# stm32_debug_adapter.net
KiCad netlist of a schematic drawn in EAGLE
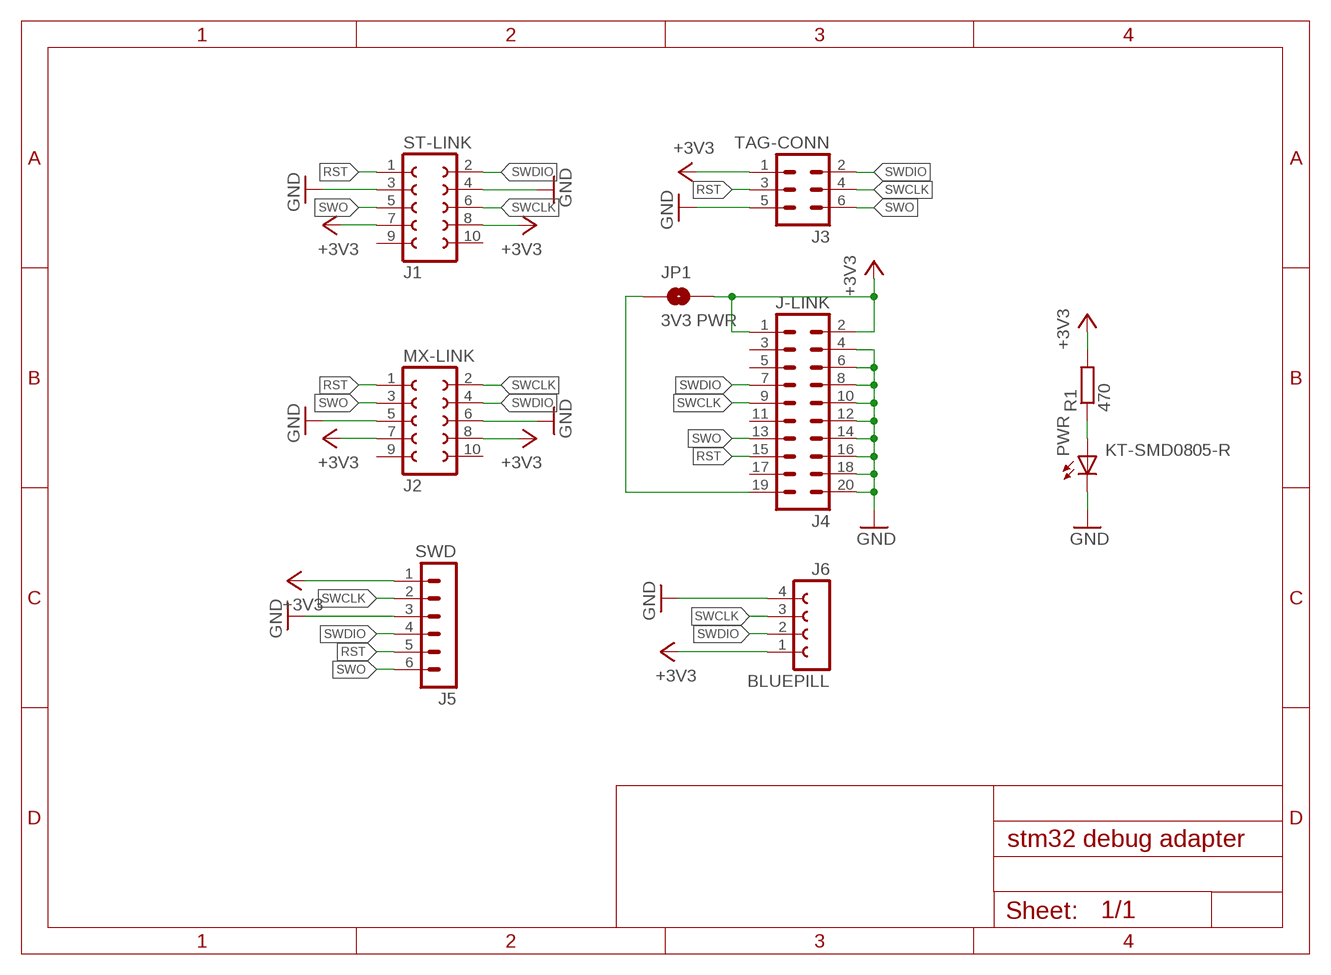
[diagram p0: schematic, sheet 1]

(export (version "E")
  (design (tool "Eeschema 10.0.6"))
  (components
    (comp (ref "J1")
      (value "ST-LINK")
      (footprint "eagle-import:FE05-2W")
      (libsource (lib "eagle-import") (part "FE05-2W"))
    )
    (comp (ref "J2")
      (value "MX-LINK")
      (footprint "eagle-import:FE05-2W")
      (libsource (lib "eagle-import") (part "FE05-2W"))
    )
    (comp (ref "J3")
      (value "TAG-CONN")
      (footprint "eagle-import:ML6")
      (libsource (lib "eagle-import") (part "ML6"))
    )
    (comp (ref "J4")
      (value "J-LINK")
      (footprint "eagle-import:ML20")
      (libsource (lib "eagle-import") (part "ML20"))
    )
    (comp (ref "J5")
      (value "SWD")
      (footprint "eagle-import:MA06-1")
      (libsource (lib "eagle-import") (part "MA06-1"))
    )
    (comp (ref "J6")
      (value "BLUEPILL")
      (footprint "eagle-import:FE04W")
      (libsource (lib "eagle-import") (part "FE04W"))
    )
    (comp (ref "JP1")
      (value "3V3 PWR")
      (footprint "eagle-import:SMT-JUMPER_2_NO_NO-SILK")
      (libsource (lib "eagle-import") (part "JUMPER-SMT_2_NO_NO-SILK"))
    )
    (comp (ref "PWR")
      (value "KT-SMD0805-R")
      (footprint "eagle-import:SML0805")
      (libsource (lib "eagle-import") (part "LEDSML0805"))
    )
    (comp (ref "R1")
      (value "470")
      (footprint "eagle-import:R0805")
      (libsource (lib "eagle-import") (part "R-EU_R0805"))
    )
  )
  (nets
    (net (code "1") (name "+3V3") (class "Default")
      (node (ref "J1") (pin "7") (pinfunction "7_7") (pintype "passive"))
      (node (ref "J1") (pin "8") (pinfunction "8_8") (pintype "passive"))
      (node (ref "J2") (pin "7") (pinfunction "7_7") (pintype "passive"))
      (node (ref "J2") (pin "8") (pinfunction "8_8") (pintype "passive"))
      (node (ref "J3") (pin "1") (pinfunction "1_1") (pintype "passive"))
      (node (ref "J4") (pin "1") (pinfunction "1_1") (pintype "passive"))
      (node (ref "J4") (pin "2") (pinfunction "2_2") (pintype "passive"))
      (node (ref "J5") (pin "1") (pinfunction "1_1") (pintype "passive"))
      (node (ref "J6") (pin "1") (pinfunction "1_1") (pintype "passive"))
      (node (ref "JP1") (pin "2") (pinfunction "2_2") (pintype "passive"))
      (node (ref "R1") (pin "2") (pinfunction "2_2") (pintype "passive"))
    )
    (net (code "2") (name "GND") (class "Default")
      (node (ref "J1") (pin "3") (pinfunction "3_3") (pintype "passive"))
      (node (ref "J1") (pin "4") (pinfunction "4_4") (pintype "passive"))
      (node (ref "J2") (pin "5") (pinfunction "5_5") (pintype "passive"))
      (node (ref "J2") (pin "6") (pinfunction "6_6") (pintype "passive"))
      (node (ref "J3") (pin "5") (pinfunction "5_5") (pintype "passive"))
      (node (ref "J4") (pin "10") (pinfunction "10_10") (pintype "passive"))
      (node (ref "J4") (pin "12") (pinfunction "12_12") (pintype "passive"))
      (node (ref "J4") (pin "14") (pinfunction "14_14") (pintype "passive"))
      (node (ref "J4") (pin "16") (pinfunction "16_16") (pintype "passive"))
      (node (ref "J4") (pin "18") (pinfunction "18_18") (pintype "passive"))
      (node (ref "J4") (pin "20") (pinfunction "20_20") (pintype "passive"))
      (node (ref "J4") (pin "4") (pinfunction "4_4") (pintype "passive"))
      (node (ref "J4") (pin "6") (pinfunction "6_6") (pintype "passive"))
      (node (ref "J4") (pin "8") (pinfunction "8_8") (pintype "passive"))
      (node (ref "J5") (pin "3") (pinfunction "3_3") (pintype "passive"))
      (node (ref "J6") (pin "4") (pinfunction "4_4") (pintype "passive"))
      (node (ref "PWR") (pin "C") (pinfunction "C_C") (pintype "passive"))
    )
    (net (code "3") (name "Net-(J4-Pad19)") (class "Default")
      (node (ref "J4") (pin "19") (pinfunction "19_19") (pintype "passive"))
      (node (ref "JP1") (pin "1") (pinfunction "1_1") (pintype "passive"))
    )
    (net (code "4") (name "Net-(PWR-PadA)") (class "Default")
      (node (ref "PWR") (pin "A") (pinfunction "A_A") (pintype "passive"))
      (node (ref "R1") (pin "1") (pinfunction "1_1") (pintype "passive"))
    )
    (net (code "5") (name "RST") (class "Default")
      (node (ref "J1") (pin "1") (pinfunction "1_1") (pintype "passive"))
      (node (ref "J2") (pin "1") (pinfunction "1_1") (pintype "passive"))
      (node (ref "J3") (pin "3") (pinfunction "3_3") (pintype "passive"))
      (node (ref "J4") (pin "15") (pinfunction "15_15") (pintype "passive"))
      (node (ref "J5") (pin "5") (pinfunction "5_5") (pintype "passive"))
    )
    (net (code "6") (name "SWCLK") (class "Default")
      (node (ref "J1") (pin "6") (pinfunction "6_6") (pintype "passive"))
      (node (ref "J2") (pin "2") (pinfunction "2_2") (pintype "passive"))
      (node (ref "J3") (pin "4") (pinfunction "4_4") (pintype "passive"))
      (node (ref "J4") (pin "9") (pinfunction "9_9") (pintype "passive"))
      (node (ref "J5") (pin "2") (pinfunction "2_2") (pintype "passive"))
      (node (ref "J6") (pin "3") (pinfunction "3_3") (pintype "passive"))
    )
    (net (code "7") (name "SWDIO") (class "Default")
      (node (ref "J1") (pin "2") (pinfunction "2_2") (pintype "passive"))
      (node (ref "J2") (pin "4") (pinfunction "4_4") (pintype "passive"))
      (node (ref "J3") (pin "2") (pinfunction "2_2") (pintype "passive"))
      (node (ref "J4") (pin "7") (pinfunction "7_7") (pintype "passive"))
      (node (ref "J5") (pin "4") (pinfunction "4_4") (pintype "passive"))
      (node (ref "J6") (pin "2") (pinfunction "2_2") (pintype "passive"))
    )
    (net (code "8") (name "SWO") (class "Default")
      (node (ref "J1") (pin "5") (pinfunction "5_5") (pintype "passive"))
      (node (ref "J2") (pin "3") (pinfunction "3_3") (pintype "passive"))
      (node (ref "J3") (pin "6") (pinfunction "6_6") (pintype "passive"))
      (node (ref "J4") (pin "13") (pinfunction "13_13") (pintype "passive"))
      (node (ref "J5") (pin "6") (pinfunction "6_6") (pintype "passive"))
    )
    (net (code "9") (name "unconnected-(J1-Pad9)") (class "Default")
      (node (ref "J1") (pin "9") (pinfunction "9_9") (pintype "passive"))
    )
    (net (code "10") (name "unconnected-(J1-Pad10)") (class "Default")
      (node (ref "J1") (pin "10") (pinfunction "10_10") (pintype "passive"))
    )
    (net (code "11") (name "unconnected-(J2-Pad9)") (class "Default")
      (node (ref "J2") (pin "9") (pinfunction "9_9") (pintype "passive"))
    )
    (net (code "12") (name "unconnected-(J2-Pad10)") (class "Default")
      (node (ref "J2") (pin "10") (pinfunction "10_10") (pintype "passive"))
    )
    (net (code "13") (name "unconnected-(J4-Pad3)") (class "Default")
      (node (ref "J4") (pin "3") (pinfunction "3_3") (pintype "passive"))
    )
    (net (code "14") (name "unconnected-(J4-Pad5)") (class "Default")
      (node (ref "J4") (pin "5") (pinfunction "5_5") (pintype "passive"))
    )
    (net (code "15") (name "unconnected-(J4-Pad11)") (class "Default")
      (node (ref "J4") (pin "11") (pinfunction "11_11") (pintype "passive"))
    )
    (net (code "16") (name "unconnected-(J4-Pad17)") (class "Default")
      (node (ref "J4") (pin "17") (pinfunction "17_17") (pintype "passive"))
    )
  )
)
